# ADF4351_10X2_v1.net
KiCad netlist of a schematic drawn in Altium Designer
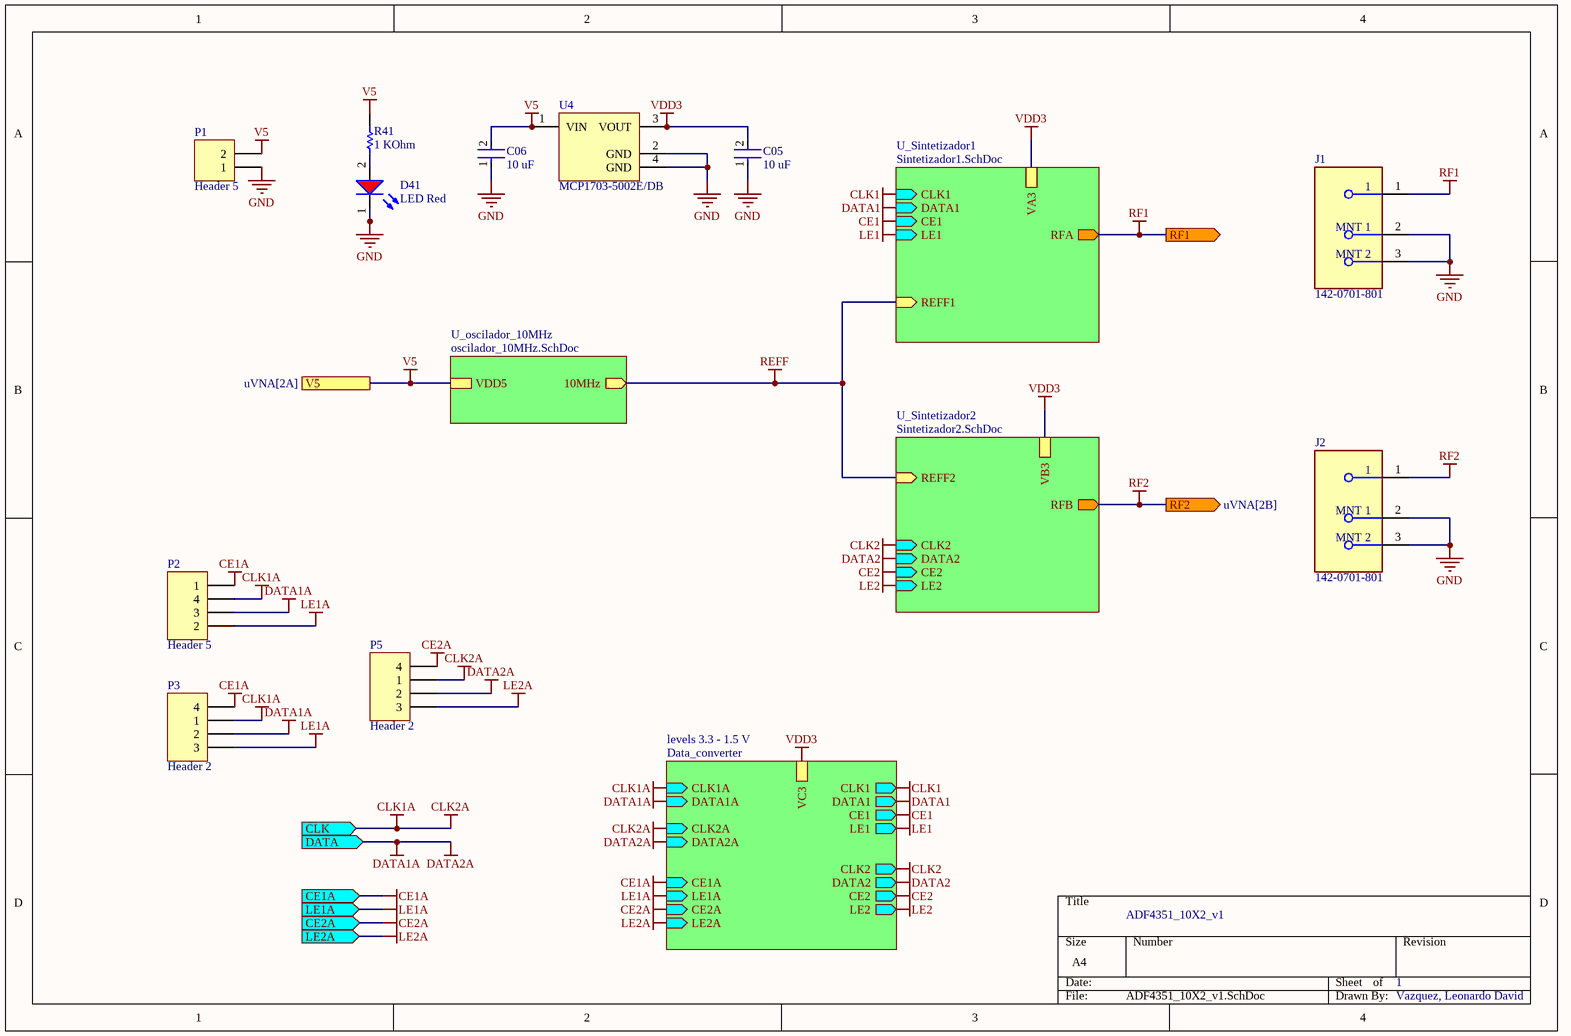
[diagram p0: ADF4351_10X2_v1.SchDoc]

(export (version "E")
  (design (tool "Eeschema 10.0.6"))
  (components
    (comp (ref "C05")
      (value "10 uF")
      (footprint "FP-CC0805-0_85-MFG")
      (description "CAP CER 0.1UF 50V X7R 0805")
      (fields (field (name "TOLERANCE") "0.1") (field (name "MANUFACTURER PART NUMBER") "CC0805KRX7R9BB104"))
      (libsource (lib "Altium Content Vault") (part "11868f565c42a9108669ba33697ecf6"))
    )
    (comp (ref "C06")
      (value "10 uF")
      (footprint "FP-CC0805-0_85-MFG")
      (description "CAP CER 0.1UF 50V X7R 0805")
      (fields (field (name "TOLERANCE") "0.1") (field (name "MANUFACTURER PART NUMBER") "CC0805KRX7R9BB104"))
      (libsource (lib "Altium Content Vault") (part "11868f565c42a9108669ba33697ecf6"))
    )
    (comp (ref "D41")
      (value "LED Red")
      (footprint "WL-SMCW_0805_150080xx75000")
      (libsource (lib "Altium Content Vault") (part "LED_Red_2A-1K"))
    )
    (comp (ref "J1")
      (value "142-0701-801")
      (footprint "FP-142-0701-801-MFG")
      (description "CONN SMA JACK STR 50OHM EDGE MNT")
      (libsource (lib "Altium Content Vault") (part "89929399afe843c8b6880c6cbd0f99a"))
    )
    (comp (ref "J2")
      (value "142-0701-801")
      (footprint "FP-142-0701-801-MFG")
      (description "CONN SMA JACK STR 50OHM EDGE MNT")
      (libsource (lib "Altium Content Vault") (part "89929399afe843c8b6880c6cbd0f99a"))
    )
    (comp (ref "P1")
      (value "Header 5")
      (footprint "HDR1X5")
      (description "Header, 2-Pin")
      (fields (field (name "PUBLISHER") "Altium Limited"))
      (libsource (lib "Miscellaneous Connectors") (part "Header 2"))
    )
    (comp (ref "P2")
      (value "Header 5")
      (footprint "HDR1X5")
      (description "Header, 4-Pin")
      (fields (field (name "PUBLISHER") "Altium Limited"))
      (libsource (lib "Miscellaneous Connectors") (part "Header 4"))
    )
    (comp (ref "P3")
      (value "Header 2")
      (footprint "HDR1X2")
      (description "Header, 4-Pin")
      (fields (field (name "PUBLISHER") "Altium Limited"))
      (libsource (lib "") (part "Header 4_1"))
    )
    (comp (ref "P5")
      (value "Header 2")
      (footprint "HDR1X2")
      (description "Header, 4-Pin")
      (fields (field (name "PUBLISHER") "Altium Limited"))
      (libsource (lib "") (part "Header 4_1"))
    )
    (comp (ref "R41")
      (value "1 KOhm")
      (footprint "RESC2013X60X40ML20T25")
      (fields (field (name "MANUFACTURER") "Panasonic") (field (name "PART NUMBER") "ERA6AEB101V"))
      (libsource (lib "Altium Content Vault") (part "RES"))
    )
    (comp (ref "U4")
      (value "MCP1703-5002E/DB")
      (footprint "SOT-223-DB3_N")
      (description "250 mA, 16V, Low Quiescent Current LDO Regulator, 3-Pin SOT-223, Extended Temperature")
      (fields (field (name "PUBLISHER") "Altium Limited"))
      (libsource (lib "Microchip Power Mgt Line Regulator") (part "MCP1703-5002E/DB"))
    )
  )
  (nets
    (net (code "2") (name "CE1A") (class "Default")
      (node (ref "P2") (pin "1") (pinfunction "1_1") (pintype "passive"))
      (node (ref "P3") (pin "4") (pinfunction "4_4") (pintype "passive"))
    )
    (net (code "4") (name "CE2A") (class "Default")
      (node (ref "P5") (pin "4") (pinfunction "4_4") (pintype "passive"))
    )
    (net (code "6") (name "CLK1A") (class "Default")
      (node (ref "P2") (pin "4") (pinfunction "4_4") (pintype "passive"))
      (node (ref "P3") (pin "1") (pinfunction "1_1") (pintype "passive"))
      (node (ref "P5") (pin "1") (pinfunction "1_1") (pintype "passive"))
    )
    (net (code "9") (name "DATA1A") (class "Default")
      (node (ref "P2") (pin "3") (pinfunction "3_3") (pintype "passive"))
      (node (ref "P3") (pin "2") (pinfunction "2_2") (pintype "passive"))
      (node (ref "P5") (pin "2") (pinfunction "2_2") (pintype "passive"))
    )
    (net (code "11") (name "GND") (class "Default")
      (node (ref "C05") (pin "1") (pinfunction "1_1") (pintype "passive"))
      (node (ref "C06") (pin "1") (pinfunction "1_1") (pintype "passive"))
      (node (ref "D41") (pin "1") (pinfunction "K_1") (pintype "passive"))
      (node (ref "J1") (pin "2") (pinfunction "MNT_1_2") (pintype "passive"))
      (node (ref "J1") (pin "3") (pinfunction "MNT_2_3") (pintype "passive"))
      (node (ref "J2") (pin "2") (pinfunction "MNT_1_2") (pintype "passive"))
      (node (ref "J2") (pin "3") (pinfunction "MNT_2_3") (pintype "passive"))
      (node (ref "P1") (pin "1") (pinfunction "1_1") (pintype "passive"))
      (node (ref "U4") (pin "2") (pinfunction "GND_2") (pintype "power_in"))
      (node (ref "U4") (pin "4") (pinfunction "GND_4") (pintype "power_in"))
    )
    (net (code "13") (name "LE1A") (class "Default")
      (node (ref "P2") (pin "2") (pinfunction "2_2") (pintype "passive"))
      (node (ref "P3") (pin "3") (pinfunction "3_3") (pintype "passive"))
    )
    (net (code "15") (name "LE2A") (class "Default")
      (node (ref "P5") (pin "3") (pinfunction "3_3") (pintype "passive"))
    )
    (net (code "16") (name "Net-(D41-A)") (class "Default")
      (node (ref "D41") (pin "2") (pinfunction "A_2") (pintype "passive"))
      (node (ref "R41") (pin "1") (pinfunction "1_1") (pintype "passive"))
    )
    (net (code "18") (name "RF1") (class "Default")
      (node (ref "J1") (pin "1") (pinfunction "1_1") (pintype "passive"))
    )
    (net (code "19") (name "RF2") (class "Default")
      (node (ref "J2") (pin "1") (pinfunction "1_1") (pintype "passive"))
    )
    (net (code "20") (name "V5") (class "Default")
      (node (ref "C06") (pin "2") (pinfunction "2_2") (pintype "passive"))
      (node (ref "P1") (pin "2") (pinfunction "2_2") (pintype "passive"))
      (node (ref "R41") (pin "2") (pinfunction "2_2") (pintype "passive"))
      (node (ref "U4") (pin "1") (pinfunction "VIN_1") (pintype "power_in"))
    )
    (net (code "21") (name "VDD3") (class "Default")
      (node (ref "C05") (pin "2") (pinfunction "2_2") (pintype "passive"))
      (node (ref "U4") (pin "3") (pinfunction "VOUT_3") (pintype "power_in"))
    )
  )
)
